# SUP_3_3_FMC.net
KiCad netlist of a schematic drawn in Altium Designer
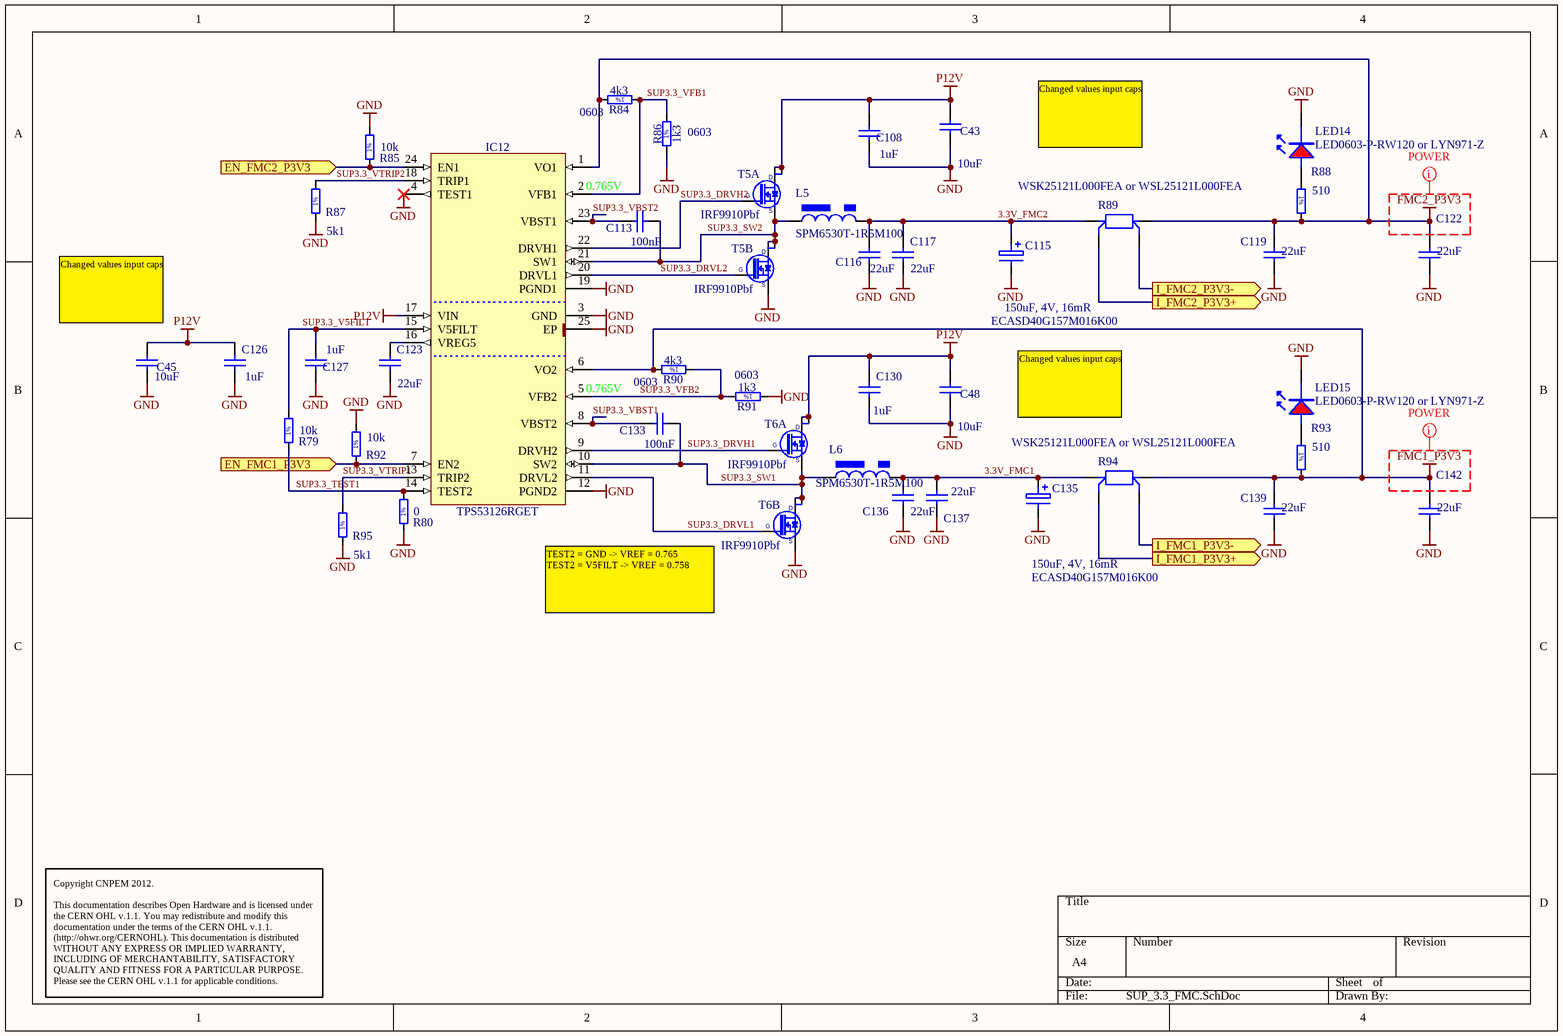
[diagram p0: SUP_3.3_FMC.SchDoc]

(export (version "E")
  (design (tool "Eeschema 10.0.6"))
  (components
    (comp (ref "C43")
      (value "10uF")
      (footprint "CAPC2012X135N")
      (description "Non-polarised capacitor")
      (fields
        (field (name "PART NUMBER") "CC0805_10UF_16V_10%_X5R")
        (field (name "VOLTAGE") "16V")
        (field (name "AUTHOR") "CERN DEM JLC")
      )
      (libsource (lib "Capacitors") (part "Capacitor - non polarized"))
    )
    (comp (ref "C45")
      (value "10uF")
      (footprint "CAPC2012X135N")
      (description "Non-polarised capacitor")
      (fields
        (field (name "PART NUMBER") "CC0805_10UF_16V_10%_X5R")
        (field (name "VOLTAGE") "16V")
        (field (name "AUTHOR") "CERN DEM JLC")
      )
      (libsource (lib "Capacitors") (part "Capacitor - non polarized"))
    )
    (comp (ref "C48")
      (value "10uF")
      (footprint "CAPC2012X135N")
      (description "Non-polarised capacitor")
      (fields
        (field (name "PART NUMBER") "CC0805_10UF_16V_10%_X5R")
        (field (name "VOLTAGE") "16V")
        (field (name "AUTHOR") "CERN DEM JLC")
      )
      (libsource (lib "Capacitors") (part "Capacitor - non polarized"))
    )
    (comp (ref "C108")
      (value "1uF")
      (footprint "CAPC1608X87N")
      (description "Non-polarised capacitor")
      (fields
        (field (name "PART NUMBER") "CC0603_1UF_16V_10%_X7R")
        (field (name "VOLTAGE") "16V")
        (field (name "AUTHOR") "CERN DEM JLC")
      )
      (libsource (lib "Capacitors") (part "Capacitor - non polarized"))
    )
    (comp (ref "C113")
      (value "100nF")
      (footprint "CAPC1005X55N")
      (description "Non-polarised capacitor")
      (fields
        (field (name "PART NUMBER") "CC0402_100NF_16V_10%_X7R")
        (field (name "VOLTAGE") "16V")
        (field (name "AUTHOR") "CERN DEM JLC")
      )
      (libsource (lib "Capacitors") (part "Capacitor - non polarized"))
    )
    (comp (ref "C115")
      (value "ECASD40G157M016K00")
      (footprint "2917_POLY")
      (description "POLY, 150uF, 4V, ESR: 16mR")
      (fields (field (name "ALTIUM_VALUE") "150uF, 4V, 16mR"))
      (libsource (lib "LIBRARY_SCH") (part "CAP_POLYMER_SMDD"))
    )
    (comp (ref "C116")
      (value "22uF")
      (footprint "CAPC3216X180N")
      (description "Non-polarised capacitor")
      (fields
        (field (name "PART NUMBER") "CC1206_22UF_10V_10%_X7R")
        (field (name "VOLTAGE") "10V")
        (field (name "AUTHOR") "CERN DEM JLC")
      )
      (libsource (lib "Capacitors") (part "Capacitor - non polarized"))
    )
    (comp (ref "C117")
      (value "22uF")
      (footprint "CAPC3216X180N")
      (description "Non-polarised capacitor")
      (fields
        (field (name "PART NUMBER") "CC1206_22UF_10V_10%_X7R")
        (field (name "VOLTAGE") "10V")
        (field (name "AUTHOR") "CERN DEM JLC")
      )
      (libsource (lib "Capacitors") (part "Capacitor - non polarized"))
    )
    (comp (ref "C119")
      (value "22uF")
      (footprint "CAPC3216X180N")
      (description "Non-polarised capacitor")
      (fields
        (field (name "PART NUMBER") "CC1206_22UF_10V_10%_X7R")
        (field (name "VOLTAGE") "10V")
        (field (name "AUTHOR") "CERN DEM JLC")
      )
      (libsource (lib "Capacitors") (part "Capacitor - non polarized"))
    )
    (comp (ref "C122")
      (value "22uF")
      (footprint "CAPC3216X180N")
      (description "Non-polarised capacitor")
      (fields
        (field (name "PART NUMBER") "CC1206_22UF_10V_10%_X7R")
        (field (name "VOLTAGE") "10V")
        (field (name "AUTHOR") "CERN DEM JLC")
      )
      (libsource (lib "Capacitors") (part "Capacitor - non polarized"))
    )
    (comp (ref "C123")
      (value "22uF")
      (footprint "CAPC3216X180N")
      (description "Non-polarised capacitor")
      (fields
        (field (name "PART NUMBER") "CC1206_22UF_10V_10%_X7R")
        (field (name "VOLTAGE") "10V")
        (field (name "AUTHOR") "CERN DEM JLC")
      )
      (libsource (lib "Capacitors") (part "Capacitor - non polarized"))
    )
    (comp (ref "C126")
      (value "1uF")
      (footprint "CAPC1608X87N")
      (description "Non-polarised capacitor")
      (fields
        (field (name "PART NUMBER") "CC0603_1UF_16V_10%_X7R")
        (field (name "VOLTAGE") "16V")
        (field (name "AUTHOR") "CERN DEM JLC")
      )
      (libsource (lib "Capacitors") (part "Capacitor - non polarized"))
    )
    (comp (ref "C127")
      (value "1uF")
      (footprint "CAPC1608X87N")
      (description "Non-polarised capacitor")
      (fields
        (field (name "PART NUMBER") "CC0603_1UF_16V_10%_X7R")
        (field (name "VOLTAGE") "16V")
        (field (name "AUTHOR") "CERN DEM JLC")
      )
      (libsource (lib "Capacitors") (part "Capacitor - non polarized"))
    )
    (comp (ref "C130")
      (value "1uF")
      (footprint "CAPC1608X87N")
      (description "Non-polarised capacitor")
      (fields
        (field (name "PART NUMBER") "CC0603_1UF_16V_10%_X7R")
        (field (name "VOLTAGE") "16V")
        (field (name "AUTHOR") "CERN DEM JLC")
      )
      (libsource (lib "Capacitors") (part "Capacitor - non polarized"))
    )
    (comp (ref "C133")
      (value "100nF")
      (footprint "CAPC1005X55N")
      (description "Non-polarised capacitor")
      (fields
        (field (name "PART NUMBER") "CC0402_100NF_16V_10%_X7R")
        (field (name "VOLTAGE") "16V")
        (field (name "AUTHOR") "CERN DEM JLC")
      )
      (libsource (lib "Capacitors") (part "Capacitor - non polarized"))
    )
    (comp (ref "C135")
      (value "ECASD40G157M016K00")
      (footprint "2917_POLY")
      (description "POLY, 150uF, 4V, ESR: 16mR")
      (fields (field (name "ALTIUM_VALUE") "150uF, 4V, 16mR"))
      (libsource (lib "LIBRARY_SCH") (part "CAP_POLYMER_SMDD"))
    )
    (comp (ref "C136")
      (value "22uF")
      (footprint "CAPC3216X180N")
      (description "Non-polarised capacitor")
      (fields
        (field (name "PART NUMBER") "CC1206_22UF_10V_10%_X7R")
        (field (name "VOLTAGE") "10V")
        (field (name "AUTHOR") "CERN DEM JLC")
      )
      (libsource (lib "Capacitors") (part "Capacitor - non polarized"))
    )
    (comp (ref "C137")
      (value "22uF")
      (footprint "CAPC3216X180N")
      (description "Non-polarised capacitor")
      (fields
        (field (name "PART NUMBER") "CC1206_22UF_10V_10%_X7R")
        (field (name "VOLTAGE") "10V")
        (field (name "AUTHOR") "CERN DEM JLC")
      )
      (libsource (lib "Capacitors") (part "Capacitor - non polarized"))
    )
    (comp (ref "C139")
      (value "22uF")
      (footprint "CAPC3216X180N")
      (description "Non-polarised capacitor")
      (fields
        (field (name "PART NUMBER") "CC1206_22UF_10V_10%_X7R")
        (field (name "VOLTAGE") "10V")
        (field (name "AUTHOR") "CERN DEM JLC")
      )
      (libsource (lib "Capacitors") (part "Capacitor - non polarized"))
    )
    (comp (ref "C142")
      (value "22uF")
      (footprint "CAPC3216X180N")
      (description "Non-polarised capacitor")
      (fields
        (field (name "PART NUMBER") "CC1206_22UF_10V_10%_X7R")
        (field (name "VOLTAGE") "10V")
        (field (name "AUTHOR") "CERN DEM JLC")
      )
      (libsource (lib "Capacitors") (part "Capacitor - non polarized"))
    )
    (comp (ref "IC12")
      (value "TPS53126RGET")
      (footprint "QFN50P400X400X100-25N-S255")
      (description "Dual Synchronous Step-Down Controller For Low Voltage Power Rails")
      (fields (field (name "MANUFACTURER") "TEXAS INSTRUMENTS") (field (name "AUTHOR") "CERN DEM JLC"))
      (libsource (lib "ICs And Semiconductors") (part "TPS53126RGET"))
    )
    (comp (ref "L5")
      (value "SPM6530T-1R5M100")
      (footprint "IND_TDK_SPM6530")
      (description "1.5uH, 20%, 10mR, 11.5A")
      (libsource (lib "LIBRARY_SCH") (part "L_POWER_SPM6530T"))
    )
    (comp (ref "L6")
      (value "SPM6530T-1R5M100")
      (footprint "IND_TDK_SPM6530")
      (description "1.5uH, 20%, 10mR, 11.5A")
      (libsource (lib "LIBRARY_SCH") (part "L_POWER_SPM6530T"))
    )
    (comp (ref "LED14")
      (value "LED0603-P-RW120 or LYN971-Z")
      (footprint "led_0603R")
      (description "LED 0603 red")
      (libsource (lib "LIBRARY_SCH") (part "LED_0603R"))
    )
    (comp (ref "LED15")
      (value "LED0603-P-RW120 or LYN971-Z")
      (footprint "led_0603R")
      (description "LED 0603 red")
      (libsource (lib "LIBRARY_SCH") (part "LED_0603R"))
    )
    (comp (ref "R79")
      (value "10k")
      (footprint "RESC1005X40N")
      (description "Resistor - 1%")
      (fields
        (field (name "PART NUMBER") "R0402_10K_1%_0.0625W_100PPM")
        (field (name "POWER") "0.0625W")
        (field (name "AUTHOR") "CERN DEM JLC")
      )
      (libsource (lib "Resistors") (part "Resistor - 1%"))
    )
    (comp (ref "R80")
      (value "0")
      (footprint "RESC1005X40N")
      (description "Resistor - 1%")
      (fields
        (field (name "PART NUMBER") "R0402_0R_JUMPER")
        (field (name "MANUFACTURER") "GENERIC")
        (field (name "AUTHOR") "CERN DEM JLC")
      )
      (libsource (lib "Resistors") (part "Resistor - 1%"))
    )
    (comp (ref "R84")
      (value "4k3")
      (footprint "RESC1608X55N")
      (description "Resistor - 1%")
      (fields
        (field (name "PART NUMBER") "R0603_4K3_1%_0.1W_100PPM")
        (field (name "POWER") "0.1W")
        (field (name "CASE") "0603")
        (field (name "AUTHOR") "CERN DEM JLC")
      )
      (libsource (lib "Resistors") (part "Resistor - 1%"))
    )
    (comp (ref "R85")
      (value "10k")
      (footprint "RESC1005X40N")
      (description "Resistor - 1%")
      (fields
        (field (name "PART NUMBER") "R0402_10K_1%_0.0625W_100PPM")
        (field (name "POWER") "0.0625W")
        (field (name "AUTHOR") "CERN DEM JLC")
      )
      (libsource (lib "Resistors") (part "Resistor - 1%"))
    )
    (comp (ref "R86")
      (value "1k3")
      (footprint "RESC1608X55N")
      (description "Resistor - 1%")
      (fields
        (field (name "PART NUMBER") "R0603_1K3_1%_0.1W_100PPM")
        (field (name "POWER") "0.1W")
        (field (name "CASE") "0603")
        (field (name "AUTHOR") "CERN DEM JLC")
      )
      (libsource (lib "Resistors") (part "Resistor - 1%"))
    )
    (comp (ref "R87")
      (value "5k1")
      (footprint "RESC1608X55N")
      (description "Resistor - 1%")
      (fields
        (field (name "PART NUMBER") "R0603_5K1_1%_0.1W_100PPM")
        (field (name "POWER") "0.1W")
        (field (name "AUTHOR") "CERN DEM JLC")
      )
      (libsource (lib "Resistors") (part "Resistor - 1%"))
    )
    (comp (ref "R88")
      (value "510")
      (footprint "RESC1005X40N")
      (description "Resistor - 1%")
      (fields
        (field (name "PART NUMBER") "R0402_510R_1%_0.0625W_100PPM")
        (field (name "POWER") "0.0625W")
        (field (name "AUTHOR") "CERN DEM JLC")
      )
      (libsource (lib "Resistors") (part "Resistor - 1%"))
    )
    (comp (ref "R89")
      (value "WSK25121L000FEA or WSL25121L000FEA")
      (footprint "RES_WSK2512")
      (description "RESISTOR, METAL STRIP, 0.001 OHM 1%")
      (libsource (lib "LIBRARY_SCH") (part "RES_POW_Kelvin"))
    )
    (comp (ref "R90")
      (value "4k3")
      (footprint "RESC1608X55N")
      (description "Resistor - 1%")
      (fields
        (field (name "PART NUMBER") "R0603_4K3_1%_0.1W_100PPM")
        (field (name "POWER") "0.1W")
        (field (name "CASE") "0603")
        (field (name "AUTHOR") "CERN DEM JLC")
      )
      (libsource (lib "Resistors") (part "Resistor - 1%"))
    )
    (comp (ref "R91")
      (value "1k3")
      (footprint "RESC1608X55N")
      (description "Resistor - 1%")
      (fields
        (field (name "PART NUMBER") "R0603_1K3_1%_0.1W_100PPM")
        (field (name "POWER") "0.1W")
        (field (name "CASE") "0603")
        (field (name "AUTHOR") "CERN DEM JLC")
      )
      (libsource (lib "Resistors") (part "Resistor - 1%"))
    )
    (comp (ref "R92")
      (value "10k")
      (footprint "RESC1005X40N")
      (description "Resistor - 1%")
      (fields
        (field (name "PART NUMBER") "R0402_10K_1%_0.0625W_100PPM")
        (field (name "POWER") "0.0625W")
        (field (name "AUTHOR") "CERN DEM JLC")
      )
      (libsource (lib "Resistors") (part "Resistor - 1%"))
    )
    (comp (ref "R93")
      (value "510")
      (footprint "RESC1005X40N")
      (description "Resistor - 1%")
      (fields
        (field (name "PART NUMBER") "R0402_510R_1%_0.0625W_100PPM")
        (field (name "POWER") "0.0625W")
        (field (name "AUTHOR") "CERN DEM JLC")
      )
      (libsource (lib "Resistors") (part "Resistor - 1%"))
    )
    (comp (ref "R94")
      (value "WSK25121L000FEA or WSL25121L000FEA")
      (footprint "RES_WSK2512")
      (description "RESISTOR, METAL STRIP, 0.001 OHM 1%")
      (libsource (lib "LIBRARY_SCH") (part "RES_POW_Kelvin"))
    )
    (comp (ref "R95")
      (value "5k1")
      (footprint "RESC1608X55N")
      (description "Resistor - 1%")
      (fields
        (field (name "PART NUMBER") "R0603_5K1_1%_0.1W_100PPM")
        (field (name "POWER") "0.1W")
        (field (name "AUTHOR") "CERN DEM JLC")
      )
      (libsource (lib "Resistors") (part "Resistor - 1%"))
    )
    (comp (ref "T5")
      (value "IRF9910Pbf")
      (footprint "SOIC127P600X175-8N")
      (description "Dual SO-8 MOSFET For POL Cconverter")
      (fields (field (name "MANUFACTURER") "INTERNATIONAL RECTIFIER") (field (name "AUTHOR") "CERN DEM JLC"))
      (libsource (lib "ICs And Semiconductors") (part "IRF9910"))
    )
    (comp (ref "T6")
      (value "IRF9910Pbf")
      (footprint "SOIC127P600X175-8N")
      (description "Dual SO-8 MOSFET For POL Cconverter")
      (fields (field (name "MANUFACTURER") "INTERNATIONAL RECTIFIER") (field (name "AUTHOR") "CERN DEM JLC"))
      (libsource (lib "ICs And Semiconductors") (part "IRF9910"))
    )
  )
  (nets
    (net (code "1") (name "/3.3V_FMC1") (class "Default")
      (node (ref "C135") (pin "1") (pinfunction "1_1") (pintype "passive"))
      (node (ref "C136") (pin "1") (pinfunction "1_1") (pintype "passive"))
      (node (ref "C137") (pin "1") (pinfunction "1_1") (pintype "passive"))
      (node (ref "L6") (pin "2") (pintype "passive"))
      (node (ref "R94") (pin "1") (pinfunction "1_1") (pintype "passive"))
    )
    (net (code "2") (name "/3.3V_FMC2") (class "Default")
      (node (ref "C115") (pin "1") (pinfunction "1_1") (pintype "passive"))
      (node (ref "C116") (pin "1") (pinfunction "1_1") (pintype "passive"))
      (node (ref "C117") (pin "1") (pinfunction "1_1") (pintype "passive"))
      (node (ref "L5") (pin "2") (pintype "passive"))
      (node (ref "R89") (pin "1") (pinfunction "1_1") (pintype "passive"))
    )
    (net (code "3") (name "/EN_FMC1_P3V3") (class "Default")
      (node (ref "IC12") (pin "7") (pinfunction "EN2_7") (pintype "input"))
      (node (ref "R92") (pin "1") (pinfunction "1_1") (pintype "passive"))
    )
    (net (code "4") (name "/EN_FMC2_P3V3") (class "Default")
      (node (ref "IC12") (pin "24") (pinfunction "EN1_24") (pintype "input"))
      (node (ref "R85") (pin "1") (pinfunction "1_1") (pintype "passive"))
    )
    (net (code "5") (name "/I_FMC1_P3V3+") (class "Default")
      (node (ref "R94") (pin "1a") (pinfunction "1a_1a") (pintype "passive"))
    )
    (net (code "6") (name "/I_FMC1_P3V3-") (class "Default")
      (node (ref "R94") (pin "2a") (pinfunction "2a_2a") (pintype "passive"))
    )
    (net (code "7") (name "/I_FMC2_P3V3+") (class "Default")
      (node (ref "R89") (pin "1a") (pinfunction "1a_1a") (pintype "passive"))
    )
    (net (code "8") (name "/I_FMC2_P3V3-") (class "Default")
      (node (ref "R89") (pin "2a") (pinfunction "2a_2a") (pintype "passive"))
    )
    (net (code "9") (name "/SUP3.3_DRVH1") (class "Default")
      (node (ref "IC12") (pin "9") (pinfunction "DRVH2_9") (pintype "output"))
      (node (ref "T6") (pin "4") (pinfunction "G_4") (pintype "passive"))
    )
    (net (code "10") (name "/SUP3.3_DRVH2") (class "Default")
      (node (ref "IC12") (pin "22") (pinfunction "DRVH1_22") (pintype "output"))
      (node (ref "T5") (pin "4") (pinfunction "G_4") (pintype "passive"))
    )
    (net (code "11") (name "/SUP3.3_DRVL1") (class "Default")
      (node (ref "IC12") (pin "11") (pinfunction "DRVL2_11") (pintype "output"))
      (node (ref "T6") (pin "2") (pinfunction "G_2") (pintype "passive"))
    )
    (net (code "12") (name "/SUP3.3_DRVL2") (class "Default")
      (node (ref "IC12") (pin "20") (pinfunction "DRVL1_20") (pintype "output"))
      (node (ref "T5") (pin "2") (pinfunction "G_2") (pintype "passive"))
    )
    (net (code "13") (name "/SUP3.3_SW1") (class "Default")
      (node (ref "C133") (pin "1") (pinfunction "1_1") (pintype "passive"))
      (node (ref "IC12") (pin "10") (pinfunction "SW2_10") (pintype "bidirectional"))
      (node (ref "L6") (pin "1") (pintype "passive"))
      (node (ref "T6") (pin "3") (pinfunction "S_3") (pintype "passive"))
      (node (ref "T6") (pin "7") (pinfunction "D_7") (pintype "passive"))
      (node (ref "T6") (pin "8") (pinfunction "D_8") (pintype "passive"))
    )
    (net (code "14") (name "/SUP3.3_SW2") (class "Default")
      (node (ref "C113") (pin "1") (pinfunction "1_1") (pintype "passive"))
      (node (ref "IC12") (pin "21") (pinfunction "SW1_21") (pintype "bidirectional"))
      (node (ref "L5") (pin "1") (pintype "passive"))
      (node (ref "T5") (pin "3") (pinfunction "S_3") (pintype "passive"))
      (node (ref "T5") (pin "7") (pinfunction "D_7") (pintype "passive"))
      (node (ref "T5") (pin "8") (pinfunction "D_8") (pintype "passive"))
    )
    (net (code "15") (name "/SUP3.3_TEST1") (class "Default")
      (node (ref "IC12") (pin "14") (pinfunction "TEST2_14") (pintype "input"))
      (node (ref "R79") (pin "1") (pinfunction "1_1") (pintype "passive"))
      (node (ref "R80") (pin "2") (pinfunction "2_2") (pintype "passive"))
    )
    (net (code "16") (name "/SUP3.3_V5FILT") (class "Default")
      (node (ref "C127") (pin "2") (pinfunction "2_2") (pintype "passive"))
      (node (ref "IC12") (pin "15") (pinfunction "V5FILT_15") (pintype "input"))
      (node (ref "R79") (pin "2") (pinfunction "2_2") (pintype "passive"))
    )
    (net (code "17") (name "/SUP3.3_VBST1") (class "Default")
      (node (ref "C133") (pin "2") (pinfunction "2_2") (pintype "passive"))
      (node (ref "IC12") (pin "8") (pinfunction "VBST2_8") (pintype "input"))
    )
    (net (code "18") (name "/SUP3.3_VBST2") (class "Default")
      (node (ref "C113") (pin "2") (pinfunction "2_2") (pintype "passive"))
      (node (ref "IC12") (pin "23") (pinfunction "VBST1_23") (pintype "input"))
    )
    (net (code "19") (name "/SUP3.3_VFB1") (class "Default")
      (node (ref "IC12") (pin "2") (pinfunction "VFB1_2") (pintype "input"))
      (node (ref "R84") (pin "1") (pinfunction "1_1") (pintype "passive"))
      (node (ref "R86") (pin "2") (pinfunction "2_2") (pintype "passive"))
    )
    (net (code "20") (name "/SUP3.3_VFB2") (class "Default")
      (node (ref "IC12") (pin "5") (pinfunction "VFB2_5") (pintype "input"))
      (node (ref "R90") (pin "1") (pinfunction "1_1") (pintype "passive"))
      (node (ref "R91") (pin "2") (pinfunction "2_2") (pintype "passive"))
    )
    (net (code "21") (name "/SUP3.3_VTRIP1") (class "Default")
      (node (ref "IC12") (pin "13") (pinfunction "TRIP2_13") (pintype "input"))
      (node (ref "R95") (pin "2") (pinfunction "2_2") (pintype "passive"))
    )
    (net (code "22") (name "/SUP3.3_VTRIP2") (class "Default")
      (node (ref "IC12") (pin "18") (pinfunction "TRIP1_18") (pintype "input"))
      (node (ref "R87") (pin "2") (pinfunction "2_2") (pintype "passive"))
    )
    (net (code "23") (name "FMC1_P3V3") (class "Default")
      (node (ref "C139") (pin "1") (pinfunction "1_1") (pintype "passive"))
      (node (ref "C142") (pin "1") (pinfunction "1_1") (pintype "passive"))
      (node (ref "IC12") (pin "6") (pinfunction "VO2_6") (pintype "input"))
      (node (ref "R90") (pin "2") (pinfunction "2_2") (pintype "passive"))
      (node (ref "R93") (pin "2") (pinfunction "2_2") (pintype "passive"))
      (node (ref "R94") (pin "2") (pinfunction "2_2") (pintype "passive"))
    )
    (net (code "24") (name "FMC2_P3V3") (class "Default")
      (node (ref "C119") (pin "1") (pinfunction "1_1") (pintype "passive"))
      (node (ref "C122") (pin "1") (pinfunction "1_1") (pintype "passive"))
      (node (ref "IC12") (pin "1") (pinfunction "VO1_1") (pintype "input"))
      (node (ref "R84") (pin "2") (pinfunction "2_2") (pintype "passive"))
      (node (ref "R88") (pin "2") (pinfunction "2_2") (pintype "passive"))
      (node (ref "R89") (pin "2") (pinfunction "2_2") (pintype "passive"))
    )
    (net (code "25") (name "GND") (class "Default")
      (node (ref "C108") (pin "1") (pinfunction "1_1") (pintype "passive"))
      (node (ref "C115") (pin "2") (pinfunction "2_2") (pintype "passive"))
      (node (ref "C116") (pin "2") (pinfunction "2_2") (pintype "passive"))
      (node (ref "C117") (pin "2") (pinfunction "2_2") (pintype "passive"))
      (node (ref "C119") (pin "2") (pinfunction "2_2") (pintype "passive"))
      (node (ref "C122") (pin "2") (pinfunction "2_2") (pintype "passive"))
      (node (ref "C123") (pin "1") (pinfunction "1_1") (pintype "passive"))
      (node (ref "C126") (pin "1") (pinfunction "1_1") (pintype "passive"))
      (node (ref "C127") (pin "1") (pinfunction "1_1") (pintype "passive"))
      (node (ref "C130") (pin "1") (pinfunction "1_1") (pintype "passive"))
      (node (ref "C135") (pin "2") (pinfunction "2_2") (pintype "passive"))
      (node (ref "C136") (pin "2") (pinfunction "2_2") (pintype "passive"))
      (node (ref "C137") (pin "2") (pinfunction "2_2") (pintype "passive"))
      (node (ref "C139") (pin "2") (pinfunction "2_2") (pintype "passive"))
      (node (ref "C142") (pin "2") (pinfunction "2_2") (pintype "passive"))
      (node (ref "C43") (pin "1") (pinfunction "1_1") (pintype "passive"))
      (node (ref "C45") (pin "1") (pinfunction "1_1") (pintype "passive"))
      (node (ref "C48") (pin "1") (pinfunction "1_1") (pintype "passive"))
      (node (ref "IC12") (pin "12") (pinfunction "PGND2_12") (pintype "power_in"))
      (node (ref "IC12") (pin "19") (pinfunction "PGND1_19") (pintype "power_in"))
      (node (ref "IC12") (pin "25") (pinfunction "EP_25") (pintype "power_in"))
      (node (ref "IC12") (pin "3") (pinfunction "GND_3") (pintype "power_in"))
      (node (ref "IC12") (pin "4") (pinfunction "TEST1_4") (pintype "output"))
      (node (ref "LED14") (pin "K") (pinfunction "K_K") (pintype "passive"))
      (node (ref "LED15") (pin "K") (pinfunction "K_K") (pintype "passive"))
      (node (ref "R80") (pin "1") (pinfunction "1_1") (pintype "passive"))
      (node (ref "R85") (pin "2") (pinfunction "2_2") (pintype "passive"))
      (node (ref "R86") (pin "1") (pinfunction "1_1") (pintype "passive"))
      (node (ref "R87") (pin "1") (pinfunction "1_1") (pintype "passive"))
      (node (ref "R91") (pin "1") (pinfunction "1_1") (pintype "passive"))
      (node (ref "R92") (pin "2") (pinfunction "2_2") (pintype "passive"))
      (node (ref "R95") (pin "1") (pinfunction "1_1") (pintype "passive"))
      (node (ref "T5") (pin "1") (pinfunction "S_1") (pintype "passive"))
      (node (ref "T6") (pin "1") (pinfunction "S_1") (pintype "passive"))
    )
    (net (code "26") (name "Net-(IC12-VREG5)") (class "Default")
      (node (ref "C123") (pin "2") (pinfunction "2_2") (pintype "passive"))
      (node (ref "IC12") (pin "16") (pinfunction "VREG5_16") (pintype "output"))
    )
    (net (code "27") (name "Net-(LED14-PadA)") (class "Default")
      (node (ref "LED14") (pin "A") (pinfunction "A_A") (pintype "passive"))
      (node (ref "R88") (pin "1") (pinfunction "1_1") (pintype "passive"))
    )
    (net (code "28") (name "Net-(LED15-PadA)") (class "Default")
      (node (ref "LED15") (pin "A") (pinfunction "A_A") (pintype "passive"))
      (node (ref "R93") (pin "1") (pinfunction "1_1") (pintype "passive"))
    )
    (net (code "29") (name "P12V") (class "Default")
      (node (ref "C108") (pin "2") (pinfunction "2_2") (pintype "passive"))
      (node (ref "C126") (pin "2") (pinfunction "2_2") (pintype "passive"))
      (node (ref "C130") (pin "2") (pinfunction "2_2") (pintype "passive"))
      (node (ref "C43") (pin "2") (pinfunction "2_2") (pintype "passive"))
      (node (ref "C45") (pin "2") (pinfunction "2_2") (pintype "passive"))
      (node (ref "C48") (pin "2") (pinfunction "2_2") (pintype "passive"))
      (node (ref "IC12") (pin "17") (pinfunction "VIN_17") (pintype "input"))
      (node (ref "T5") (pin "5") (pinfunction "D_5") (pintype "passive"))
      (node (ref "T5") (pin "6") (pinfunction "D_6") (pintype "passive"))
      (node (ref "T6") (pin "5") (pinfunction "D_5") (pintype "passive"))
      (node (ref "T6") (pin "6") (pinfunction "D_6") (pintype "passive"))
    )
  )
)
